# T4F81_FPGA.net
KiCad netlist of a schematic drawn in Altium Designer
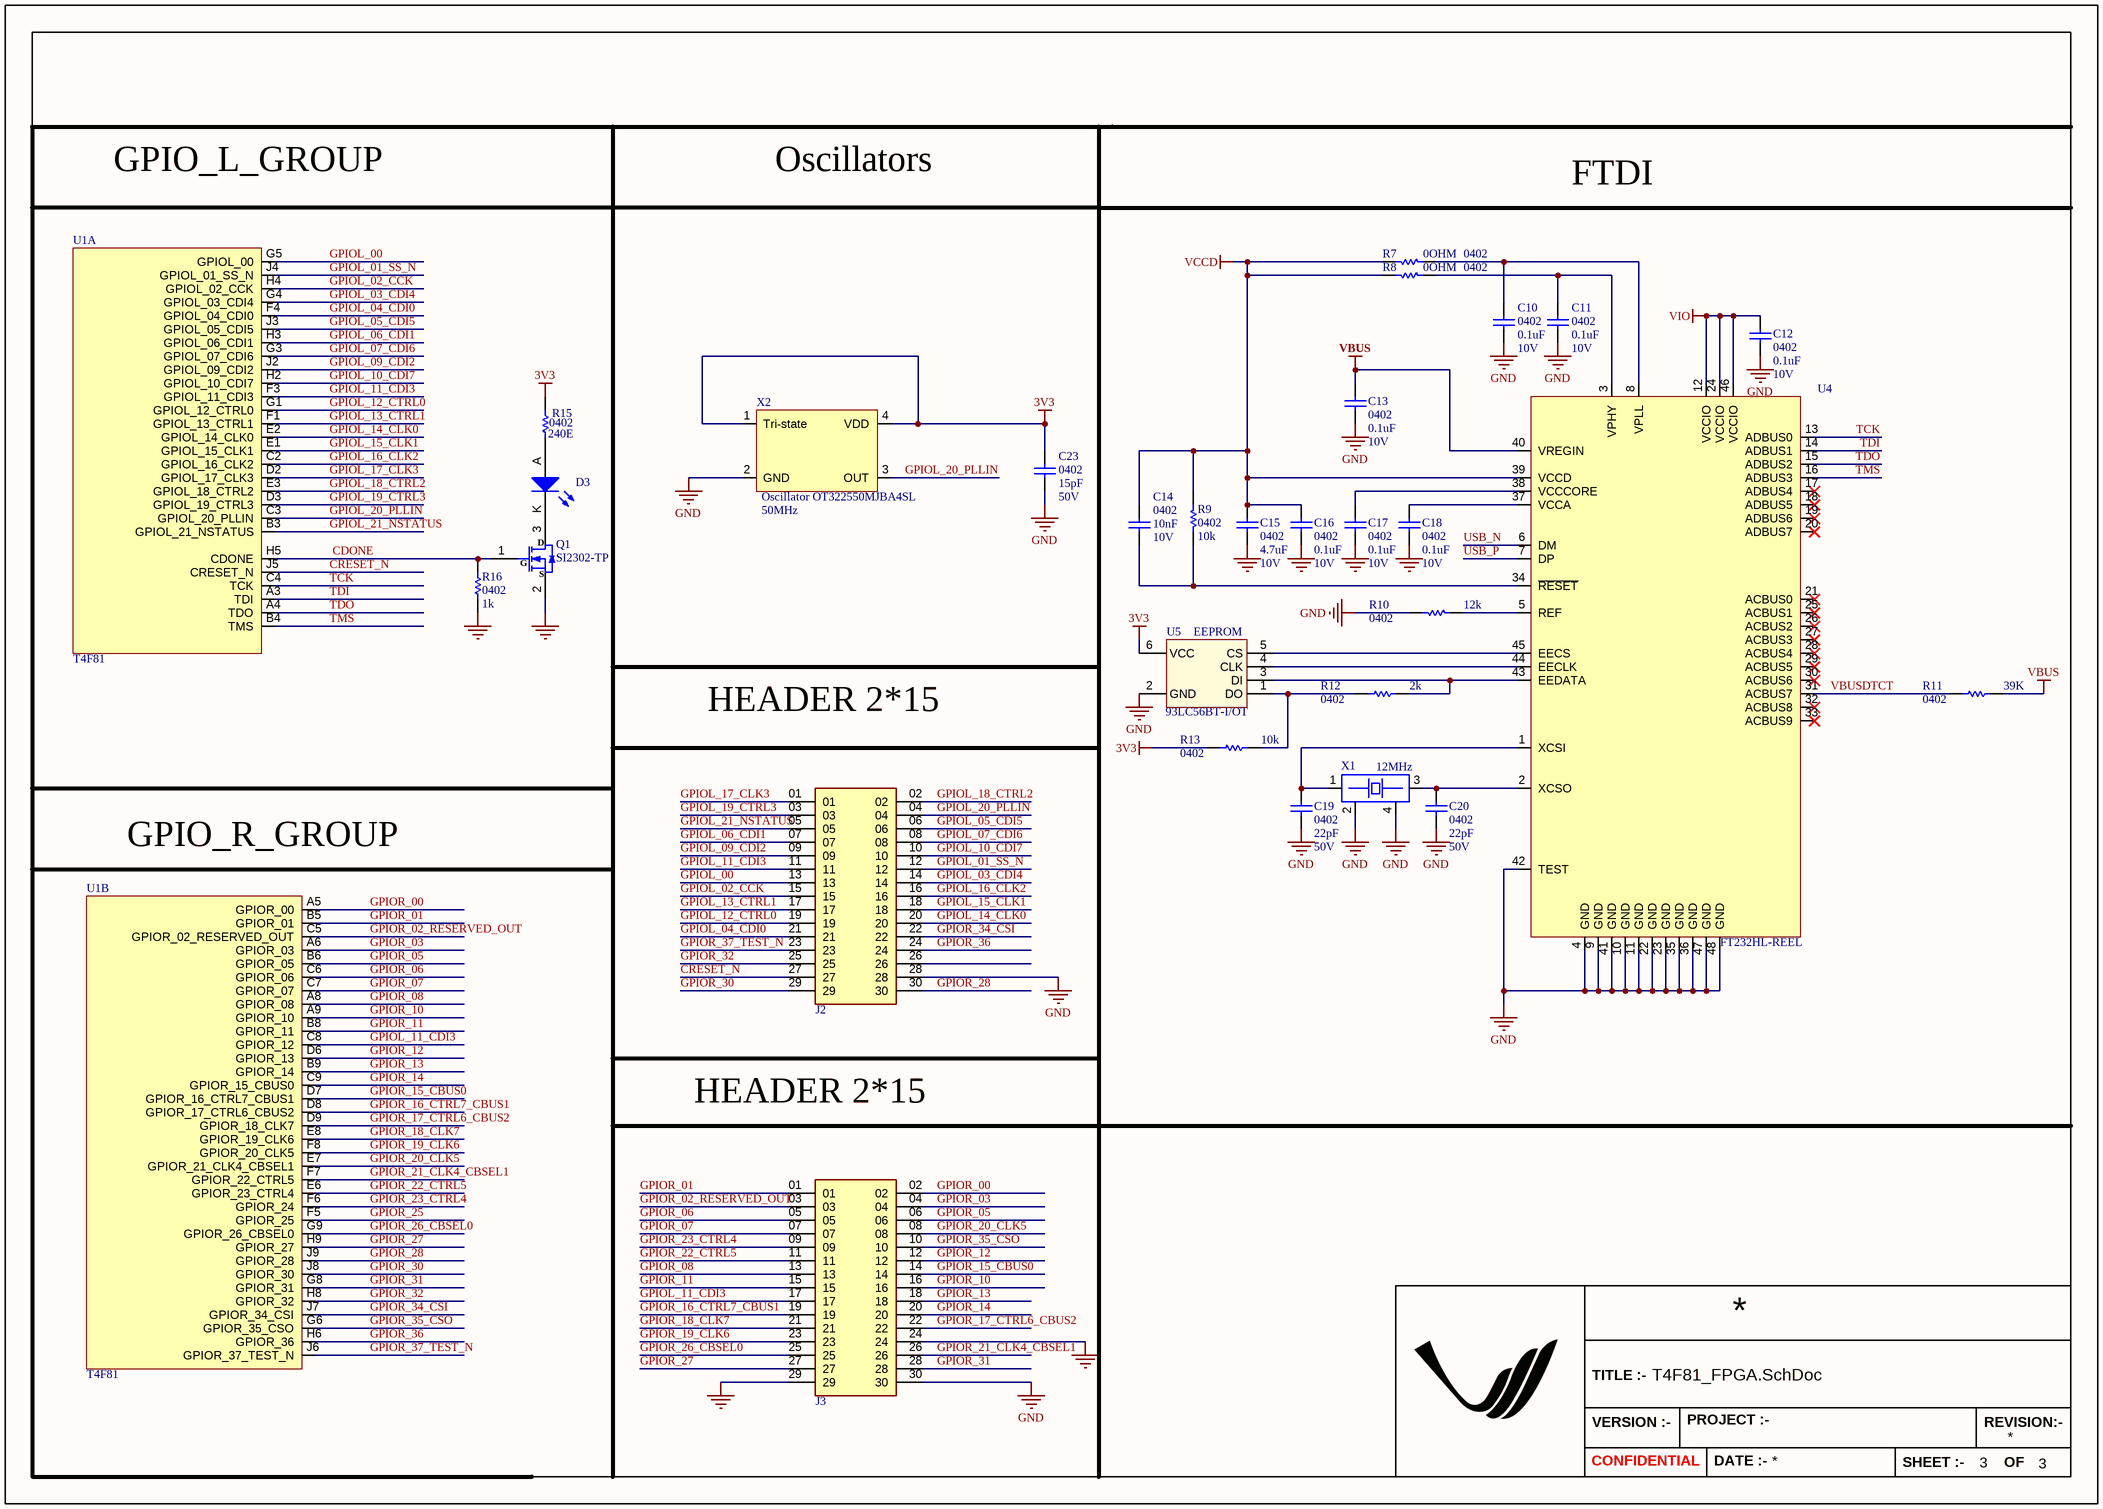
[diagram p0: T4F81_FPGA.SchDoc]

(export (version "E")
  (design (tool "Eeschema 10.0.6"))
  (components
    (comp (ref "C10")
      (value "0.1uF")
      (footprint "CAPC0402")
      (description "Ceramic Capacitor, 0.1uF, 0402,10V")
      (fields (field (name "CASE/PACKAGE") "0402") (field (name "VOLTAGE") "10V"))
      (libsource (lib "Pd's Sch Lib") (part "Capacitor"))
    )
    (comp (ref "C11")
      (value "0.1uF")
      (footprint "CAPC0402")
      (description "Ceramic Capacitor, 0.1uF, 0402,10V")
      (fields (field (name "CASE/PACKAGE") "0402") (field (name "VOLTAGE") "10V"))
      (libsource (lib "Pd's Sch Lib") (part "Capacitor"))
    )
    (comp (ref "C12")
      (value "0.1uF")
      (footprint "CAPC0402")
      (description "Ceramic Capacitor, 0.1uF, 0402,10V")
      (fields (field (name "CASE/PACKAGE") "0402") (field (name "VOLTAGE") "10V"))
      (libsource (lib "Pd's Sch Lib") (part "Capacitor"))
    )
    (comp (ref "C13")
      (value "0.1uF")
      (footprint "CAPC0402")
      (description "Ceramic Capacitor, 0.1uF, 0402,10V")
      (fields (field (name "CASE/PACKAGE") "0402") (field (name "VOLTAGE") "10V"))
      (libsource (lib "Pd's Sch Lib") (part "Capacitor"))
    )
    (comp (ref "C14")
      (value "10nF")
      (footprint "CAPC0402")
      (description "Ceramic Capacitor, 10nF, 0402,10V")
      (fields (field (name "CASE/PACKAGE") "0402") (field (name "VOLTAGE") "10V"))
      (libsource (lib "Pd's Sch Lib") (part "Capacitor"))
    )
    (comp (ref "C15")
      (value "4.7uF")
      (footprint "CAPC0402")
      (description "Ceramic Capacitor, 4.7uF, 0402,10V")
      (fields (field (name "CASE/PACKAGE") "0402") (field (name "VOLTAGE") "10V"))
      (libsource (lib "Pd's Sch Lib") (part "Capacitor"))
    )
    (comp (ref "C16")
      (value "0.1uF")
      (footprint "CAPC0402")
      (description "Ceramic Capacitor, 0.1UF, 0402,10V")
      (fields (field (name "CASE/PACKAGE") "0402") (field (name "VOLTAGE") "10V"))
      (libsource (lib "Pd's Sch Lib") (part "Capacitor"))
    )
    (comp (ref "C17")
      (value "0.1uF")
      (footprint "CAPC0402")
      (description "Ceramic Capacitor, 0.1UF, 0402,10V")
      (fields (field (name "CASE/PACKAGE") "0402") (field (name "VOLTAGE") "10V"))
      (libsource (lib "Pd's Sch Lib") (part "Capacitor"))
    )
    (comp (ref "C18")
      (value "0.1uF")
      (footprint "CAPC0402")
      (description "Ceramic Capacitor, 0.1UF, 0402,10V")
      (fields (field (name "CASE/PACKAGE") "0402") (field (name "VOLTAGE") "10V"))
      (libsource (lib "Pd's Sch Lib") (part "Capacitor"))
    )
    (comp (ref "C19")
      (value "22pF")
      (footprint "CAPC0402")
      (description "Ceramic Capacitor, 22pF, 0402,50V")
      (fields (field (name "CASE/PACKAGE") "0402") (field (name "VOLTAGE") "50V"))
      (libsource (lib "Pd's Sch Lib") (part "Capacitor"))
    )
    (comp (ref "C20")
      (value "22pF")
      (footprint "CAPC0402")
      (description "Ceramic Capacitor, 22pF, 0402,50V")
      (fields (field (name "CASE/PACKAGE") "0402") (field (name "VOLTAGE") "50V"))
      (libsource (lib "Pd's Sch Lib") (part "Capacitor"))
    )
    (comp (ref "C23")
      (value "15pF")
      (footprint "CAPC0402")
      (description "Ceramic Capacitor, 15pF, 0402,50V")
      (fields (field (name "CASE/PACKAGE") "0402") (field (name "VOLTAGE") "50V"))
      (libsource (lib "Pd's Sch Lib") (part "Capacitor"))
    )
    (comp (ref "D3")
      (value "~")
      (footprint "led_0603")
      (description "GREEN LED, 0603")
      (fields (field (name "MANUFACTURER PART NUMBER") "GREEN"))
      (libsource (lib "CUSTOM TNY290PG") (part "LED1"))
    )
    (comp (ref "J2")
      (value "Header 15X2 2.54mm")
      (footprint "Header_15X2_2.54")
      (description "Connector Header position")
      (fields (field (name "MANUFACTURER PART NUMBER") "Th P2.54MM"))
      (libsource (lib "CUSTOM SCH") (part "Header 15X2 2.54mm"))
    )
    (comp (ref "J3")
      (value "Header 15X2 2.54mm")
      (footprint "Header_15X2_2.54")
      (description "Connector Header position")
      (fields (field (name "MANUFACTURER PART NUMBER") "Th P2.54MM"))
      (libsource (lib "CUSTOM SCH") (part "Header 15X2 2.54mm"))
    )
    (comp (ref "Q1")
      (value "~")
      (footprint "SOT23-3")
      (description "N-Channel 20V 3A 1.25W (Ta) Surface Mount SOT-23")
      (fields (field (name "MANUFACTURER PART NUMBER") "SI2302-TP"))
      (libsource (lib "SchLib_SPEEDSTER7T_AC7T1500") (part "MOSFET Si2302CDS"))
    )
    (comp (ref "R7")
      (value "0OHM")
      (footprint "resc0402")
      (description "Thick Film Resistor -  0ohm, 1%, 0402")
      (fields
        (field (name "MANUFACTURER PART NUMBER") "RC0402FR-070RL")
        (field (name "CASE/PACKAGE") "0402")
        (field (name "Comment") "Res1")
      )
      (libsource (lib "Miscellaneous Devices") (part "Res1"))
    )
    (comp (ref "R8")
      (value "0OHM")
      (footprint "resc0402")
      (description "Thick Film Resistor -  0ohm, 1%, 0402")
      (fields (field (name "CASE/PACKAGE") "0402") (field (name "Comment") "Res1"))
      (libsource (lib "Miscellaneous Devices") (part "Res1"))
    )
    (comp (ref "R9")
      (value "10k")
      (footprint "RESC0402")
      (description "Thick Film Resistor -  10Kohm, 1%, 0402")
      (fields (field (name "CASE/PACKAGE") "0402") (field (name "Comment") "Res1"))
      (libsource (lib "Miscellaneous Devices") (part "Res1"))
    )
    (comp (ref "R10")
      (value "12k")
      (footprint "resc0402")
      (description "Thick Film Resistor -  12Kohm, 1%, 0402")
      (fields (field (name "CASE/PACKAGE") "0402") (field (name "Comment") "Res1"))
      (libsource (lib "Miscellaneous Devices") (part "Res1"))
    )
    (comp (ref "R11")
      (value "39K")
      (footprint "CAPC0402")
      (description "Thick Film Resistor -  39Kohm, 1%, 0402")
      (fields (field (name "CASE/PACKAGE") "0402") (field (name "Comment") "Res1"))
      (libsource (lib "Miscellaneous Devices") (part "Res1"))
    )
    (comp (ref "R12")
      (value "2k")
      (footprint "resc0402")
      (description "Thick Film Resistor -  2Kohm, 1%, 0402")
      (fields (field (name "CASE/PACKAGE") "0402") (field (name "Comment") "Res1"))
      (libsource (lib "Miscellaneous Devices") (part "Res1"))
    )
    (comp (ref "R13")
      (value "10k")
      (footprint "resc0402")
      (description "Thick Film Resistor -  10Kohm, 1%, 0402")
      (fields (field (name "CASE/PACKAGE") "0402") (field (name "Comment") "Res1"))
      (libsource (lib "Miscellaneous Devices") (part "Res1"))
    )
    (comp (ref "R15")
      (value "240E")
      (footprint "RESC0402")
      (description "Thick Film Resistor -  240ohm, 1%, 0402")
      (fields (field (name "CASE/PACKAGE") "0402"))
      (libsource (lib "CUSTOM TNY290PG") (part "Res"))
    )
    (comp (ref "R16")
      (value "1k")
      (footprint "RESC0402")
      (description "Thick Film Resistor -  1Kohm, 1%, 0402")
      (fields (field (name "CASE/PACKAGE") "0402"))
      (libsource (lib "CUSTOM TNY290PG") (part "Res"))
    )
    (comp (ref "U1") (value "T4F81") (footprint "T4F81 fpga") (libsource (lib "CUSTOM SCH") (part "T4F81")))
    (comp (ref "U4")
      (value "FTDI")
      (footprint "LQFP-48")
      (fields (field (name "MANUFACTURER PART NUMBER") "FT232HL-REEL"))
      (libsource (lib "Pd's Sch Lib") (part "FT232HL"))
    )
    (comp (ref "U5")
      (value "93LC56BT-I/OT")
      (footprint "SOT23-6")
      (description "MICROCHIP - 93LC56BT-I/OT. - 2K, 128 X 16, SERIAL EE, IND ROHS COMPLIANT: YES")
      (fields (field (name "TYPE") "EEPROM") (field (name "MANUFACTURER PART NUMBER") "93LC56BT-I/OT"))
      (libsource (lib "CUSTOM TNY290PG") (part "93LC56BT-I/OT"))
    )
    (comp (ref "X1")
      (value "XC2426TR-ND")
      (footprint "Crystal_3225")
      (description "CRYSTAL 12.0000MHZ 10PF SMD")
      (fields
        (field (name "MANUFACTURER PART NUMBER") "ECS-120-10-33B-CKM-TR")
        (field (name "FREQUENCY") "12MHz")
      )
      (libsource (lib "Pd's Sch Lib") (part "CRYSTAL_1_1"))
    )
    (comp (ref "X2")
      (value "Oscillator OT322550MJBA4SL")
      (footprint "Crystal_3225")
      (description "1.8V~3.3V -40℃~+85℃ ±10ppm 50MHz SMD3225-4P Oscillators ROHS (OT322550MJBA4SL) (C717684)")
      (fields (field (name "MANUFACTURER PART NUMBER") "OT322550MJBA4SL") (field (name "FREQUENCY") "50MHz"))
      (libsource (lib "CUSTOM SCH") (part "Oscillator OT322550MJBA4SL"))
    )
  )
  (nets
    (net (code "1") (name "/CDONE") (class "Default")
      (node (ref "Q1") (pin "1") (pinfunction "G_1") (pintype "passive"))
      (node (ref "R16") (pin "1") (pinfunction "1_1") (pintype "passive"))
      (node (ref "U1") (pin "H5") (pinfunction "CDONE_H5") (pintype "passive"))
    )
    (net (code "2") (name "/CRESET_N") (class "Default")
      (node (ref "J2") (pin "27") (pinfunction "27_27") (pintype "passive"))
      (node (ref "U1") (pin "J5") (pinfunction "CRESET_N_J5") (pintype "passive"))
    )
    (net (code "3") (name "/GPIOL_00") (class "Default")
      (node (ref "J2") (pin "13") (pinfunction "13_13") (pintype "passive"))
      (node (ref "U1") (pin "G5") (pinfunction "GPIOL_00_G5") (pintype "passive"))
    )
    (net (code "4") (name "/GPIOL_01_SS_N") (class "Default")
      (node (ref "J2") (pin "12") (pinfunction "12_12") (pintype "passive"))
      (node (ref "U1") (pin "J4") (pinfunction "GPIOL_01_SS_N_J4") (pintype "passive"))
    )
    (net (code "5") (name "/GPIOL_02_CCK") (class "Default")
      (node (ref "J2") (pin "15") (pinfunction "15_15") (pintype "passive"))
      (node (ref "U1") (pin "H4") (pinfunction "GPIOL_02_CCK_H4") (pintype "passive"))
    )
    (net (code "6") (name "/GPIOL_03_CDI4") (class "Default")
      (node (ref "J2") (pin "14") (pinfunction "14_14") (pintype "passive"))
      (node (ref "U1") (pin "G4") (pinfunction "GPIOL_03_CDI4_G4") (pintype "passive"))
    )
    (net (code "7") (name "/GPIOL_04_CDI0") (class "Default")
      (node (ref "J2") (pin "21") (pinfunction "21_21") (pintype "passive"))
      (node (ref "U1") (pin "F4") (pinfunction "GPIOL_04_CDI0_F4") (pintype "passive"))
    )
    (net (code "8") (name "/GPIOL_05_CDI5") (class "Default")
      (node (ref "J2") (pin "06") (pinfunction "06_06") (pintype "passive"))
      (node (ref "U1") (pin "J3") (pinfunction "GPIOL_05_CDI5_J3") (pintype "passive"))
    )
    (net (code "9") (name "/GPIOL_06_CDI1") (class "Default")
      (node (ref "J2") (pin "07") (pinfunction "07_07") (pintype "passive"))
      (node (ref "U1") (pin "H3") (pinfunction "GPIOL_06_CDI1_H3") (pintype "passive"))
    )
    (net (code "10") (name "/GPIOL_07_CDI6") (class "Default")
      (node (ref "J2") (pin "08") (pinfunction "08_08") (pintype "passive"))
      (node (ref "U1") (pin "G3") (pinfunction "GPIOL_07_CDI6_G3") (pintype "passive"))
    )
    (net (code "11") (name "/GPIOL_09_CDI2") (class "Default")
      (node (ref "J2") (pin "09") (pinfunction "09_09") (pintype "passive"))
      (node (ref "U1") (pin "J2") (pinfunction "GPIOL_09_CDI2_J2") (pintype "passive"))
    )
    (net (code "12") (name "/GPIOL_10_CDI7") (class "Default")
      (node (ref "J2") (pin "10") (pinfunction "10_10") (pintype "passive"))
      (node (ref "U1") (pin "H2") (pinfunction "GPIOL_10_CDI7_H2") (pintype "passive"))
    )
    (net (code "13") (name "/GPIOL_11_CDI3") (class "Default")
      (node (ref "J2") (pin "11") (pinfunction "11_11") (pintype "passive"))
      (node (ref "J3") (pin "17") (pinfunction "17_17") (pintype "passive"))
      (node (ref "U1") (pin "C8") (pinfunction "GPIOR_12_C8") (pintype "passive"))
      (node (ref "U1") (pin "F3") (pinfunction "GPIOL_11_CDI3_F3") (pintype "passive"))
    )
    (net (code "14") (name "/GPIOL_12_CTRL0") (class "Default")
      (node (ref "J2") (pin "19") (pinfunction "19_19") (pintype "passive"))
      (node (ref "U1") (pin "G1") (pinfunction "GPIOL_12_CTRL0_G1") (pintype "passive"))
    )
    (net (code "15") (name "/GPIOL_13_CTRL1") (class "Default")
      (node (ref "J2") (pin "17") (pinfunction "17_17") (pintype "passive"))
      (node (ref "U1") (pin "F1") (pinfunction "GPIOL_13_CTRL1_F1") (pintype "passive"))
    )
    (net (code "16") (name "/GPIOL_14_CLK0") (class "Default")
      (node (ref "J2") (pin "20") (pinfunction "20_20") (pintype "passive"))
      (node (ref "U1") (pin "E2") (pinfunction "GPIOL_14_CLK0_E2") (pintype "passive"))
    )
    (net (code "17") (name "/GPIOL_15_CLK1") (class "Default")
      (node (ref "J2") (pin "18") (pinfunction "18_18") (pintype "passive"))
      (node (ref "U1") (pin "E1") (pinfunction "GPIOL_15_CLK1_E1") (pintype "passive"))
    )
    (net (code "18") (name "/GPIOL_16_CLK2") (class "Default")
      (node (ref "J2") (pin "16") (pinfunction "16_16") (pintype "passive"))
      (node (ref "U1") (pin "C2") (pinfunction "GPIOL_16_CLK2_C2") (pintype "passive"))
    )
    (net (code "19") (name "/GPIOL_17_CLK3") (class "Default")
      (node (ref "J2") (pin "01") (pinfunction "01_01") (pintype "passive"))
      (node (ref "U1") (pin "D2") (pinfunction "GPIOL_17_CLK3_D2") (pintype "passive"))
    )
    (net (code "20") (name "/GPIOL_18_CTRL2") (class "Default")
      (node (ref "J2") (pin "02") (pinfunction "02_02") (pintype "passive"))
      (node (ref "U1") (pin "E3") (pinfunction "GPIOL_18_CTRL2_E3") (pintype "passive"))
    )
    (net (code "21") (name "/GPIOL_19_CTRL3") (class "Default")
      (node (ref "J2") (pin "03") (pinfunction "03_03") (pintype "passive"))
      (node (ref "U1") (pin "D3") (pinfunction "GPIOL_19_CTRL3_D3") (pintype "passive"))
    )
    (net (code "22") (name "/GPIOL_20_PLLIN") (class "Default")
      (node (ref "J2") (pin "04") (pinfunction "04_04") (pintype "passive"))
      (node (ref "U1") (pin "C3") (pinfunction "GPIOL_20_PLLIN_C3") (pintype "passive"))
      (node (ref "X2") (pin "3") (pinfunction "OUT_3") (pintype "passive"))
    )
    (net (code "23") (name "/GPIOL_21_NSTATUS") (class "Default")
      (node (ref "J2") (pin "05") (pinfunction "05_05") (pintype "passive"))
      (node (ref "U1") (pin "B3") (pinfunction "GPIOL_21_NSTATUS_B3") (pintype "passive"))
    )
    (net (code "24") (name "/GPIOR_00") (class "Default")
      (node (ref "J3") (pin "02") (pinfunction "02_02") (pintype "passive"))
      (node (ref "U1") (pin "A5") (pinfunction "GPIOR_00_A5") (pintype "passive"))
    )
    (net (code "25") (name "/GPIOR_01") (class "Default")
      (node (ref "J3") (pin "01") (pinfunction "01_01") (pintype "passive"))
      (node (ref "U1") (pin "B5") (pinfunction "GPIOR_01_B5") (pintype "passive"))
    )
    (net (code "26") (name "/GPIOR_02_RESERVED_OUT") (class "Default")
      (node (ref "J3") (pin "03") (pinfunction "03_03") (pintype "passive"))
      (node (ref "U1") (pin "C5") (pinfunction "GPIOR_02_RESERVED_OUT_C5") (pintype "passive"))
    )
    (net (code "27") (name "/GPIOR_03") (class "Default")
      (node (ref "J3") (pin "04") (pinfunction "04_04") (pintype "passive"))
      (node (ref "U1") (pin "A6") (pinfunction "GPIOR_03_A6") (pintype "passive"))
    )
    (net (code "28") (name "/GPIOR_05") (class "Default")
      (node (ref "J3") (pin "06") (pinfunction "06_06") (pintype "passive"))
      (node (ref "U1") (pin "B6") (pinfunction "GPIOR_05_B6") (pintype "passive"))
    )
    (net (code "29") (name "/GPIOR_06") (class "Default")
      (node (ref "J3") (pin "05") (pinfunction "05_05") (pintype "passive"))
      (node (ref "U1") (pin "C6") (pinfunction "GPIOR_06_C6") (pintype "passive"))
    )
    (net (code "30") (name "/GPIOR_07") (class "Default")
      (node (ref "J3") (pin "07") (pinfunction "07_07") (pintype "passive"))
      (node (ref "U1") (pin "C7") (pinfunction "GPIOR_07_C7") (pintype "passive"))
    )
    (net (code "31") (name "/GPIOR_08") (class "Default")
      (node (ref "J3") (pin "13") (pinfunction "13_13") (pintype "passive"))
      (node (ref "U1") (pin "A8") (pinfunction "GPIOR_08_A8") (pintype "passive"))
    )
    (net (code "32") (name "/GPIOR_10") (class "Default")
      (node (ref "J3") (pin "16") (pinfunction "16_16") (pintype "passive"))
      (node (ref "U1") (pin "A9") (pinfunction "GPIOR_10_A9") (pintype "passive"))
    )
    (net (code "33") (name "/GPIOR_11") (class "Default")
      (node (ref "J3") (pin "15") (pinfunction "15_15") (pintype "passive"))
      (node (ref "U1") (pin "B8") (pinfunction "GPIOR_11_B8") (pintype "passive"))
    )
    (net (code "34") (name "/GPIOR_12") (class "Default")
      (node (ref "J3") (pin "12") (pinfunction "12_12") (pintype "passive"))
      (node (ref "U1") (pin "D6") (pinfunction "GPIOR_13_D6") (pintype "passive"))
    )
    (net (code "35") (name "/GPIOR_13") (class "Default")
      (node (ref "J3") (pin "18") (pinfunction "18_18") (pintype "passive"))
      (node (ref "U1") (pin "B9") (pinfunction "GPIOR_14_B9") (pintype "passive"))
    )
    (net (code "36") (name "/GPIOR_14") (class "Default")
      (node (ref "J3") (pin "20") (pinfunction "20_20") (pintype "passive"))
      (node (ref "U1") (pin "C9") (pinfunction "GPIOR_15_CBUS0_C9") (pintype "passive"))
    )
    (net (code "37") (name "/GPIOR_15_CBUS0") (class "Default")
      (node (ref "J3") (pin "14") (pinfunction "14_14") (pintype "passive"))
      (node (ref "U1") (pin "D7") (pinfunction "GPIOR_16_CTRL7_CBUS1_D7") (pintype "passive"))
    )
    (net (code "38") (name "/GPIOR_16_CTRL7_CBUS1") (class "Default")
      (node (ref "J3") (pin "19") (pinfunction "19_19") (pintype "passive"))
      (node (ref "U1") (pin "D8") (pinfunction "GPIOR_17_CTRL6_CBUS2_D8") (pintype "passive"))
    )
    (net (code "39") (name "/GPIOR_17_CTRL6_CBUS2") (class "Default")
      (node (ref "J3") (pin "22") (pinfunction "22_22") (pintype "passive"))
      (node (ref "U1") (pin "D9") (pinfunction "GPIOR_18_CLK7_D9") (pintype "passive"))
    )
    (net (code "40") (name "/GPIOR_18_CLK7") (class "Default")
      (node (ref "J3") (pin "21") (pinfunction "21_21") (pintype "passive"))
      (node (ref "U1") (pin "E8") (pinfunction "GPIOR_19_CLK6_E8") (pintype "passive"))
    )
    (net (code "41") (name "/GPIOR_19_CLK6") (class "Default")
      (node (ref "J3") (pin "23") (pinfunction "23_23") (pintype "passive"))
      (node (ref "U1") (pin "F8") (pinfunction "GPIOR_20_CLK5_F8") (pintype "passive"))
    )
    (net (code "42") (name "/GPIOR_20_CLK5") (class "Default")
      (node (ref "J3") (pin "08") (pinfunction "08_08") (pintype "passive"))
      (node (ref "U1") (pin "E7") (pinfunction "GPIOR_21_CLK4_CBSEL1_E7") (pintype "passive"))
    )
    (net (code "43") (name "/GPIOR_21_CLK4_CBSEL1") (class "Default")
      (node (ref "J3") (pin "26") (pinfunction "26_26") (pintype "passive"))
      (node (ref "U1") (pin "F7") (pinfunction "GPIOR_22_CTRL5_F7") (pintype "passive"))
    )
    (net (code "44") (name "/GPIOR_22_CTRL5") (class "Default")
      (node (ref "J3") (pin "11") (pinfunction "11_11") (pintype "passive"))
      (node (ref "U1") (pin "E6") (pinfunction "GPIOR_23_CTRL4_E6") (pintype "passive"))
    )
    (net (code "45") (name "/GPIOR_23_CTRL4") (class "Default")
      (node (ref "J3") (pin "09") (pinfunction "09_09") (pintype "passive"))
      (node (ref "U1") (pin "F6") (pinfunction "GPIOR_24_F6") (pintype "passive"))
    )
    (net (code "46") (name "/GPIOR_25") (class "Default")
      (node (ref "U1") (pin "F5") (pinfunction "GPIOR_25_F5") (pintype "passive"))
    )
    (net (code "47") (name "/GPIOR_26_CBSEL0") (class "Default")
      (node (ref "J3") (pin "25") (pinfunction "25_25") (pintype "passive"))
      (node (ref "U1") (pin "G9") (pinfunction "GPIOR_26_CBSEL0_G9") (pintype "passive"))
    )
    (net (code "48") (name "/GPIOR_27") (class "Default")
      (node (ref "J3") (pin "27") (pinfunction "27_27") (pintype "passive"))
      (node (ref "U1") (pin "H9") (pinfunction "GPIOR_27_H9") (pintype "passive"))
    )
    (net (code "49") (name "/GPIOR_28") (class "Default")
      (node (ref "J2") (pin "30") (pinfunction "30_30") (pintype "passive"))
      (node (ref "U1") (pin "J9") (pinfunction "GPIOR_28_J9") (pintype "passive"))
    )
    (net (code "50") (name "/GPIOR_30") (class "Default")
      (node (ref "J2") (pin "29") (pinfunction "29_29") (pintype "passive"))
      (node (ref "U1") (pin "J8") (pinfunction "GPIOR_30_J8") (pintype "passive"))
    )
    (net (code "51") (name "/GPIOR_31") (class "Default")
      (node (ref "J3") (pin "28") (pinfunction "28_28") (pintype "passive"))
      (node (ref "U1") (pin "G8") (pinfunction "GPIOR_31_G8") (pintype "passive"))
    )
    (net (code "52") (name "/GPIOR_32") (class "Default")
      (node (ref "J2") (pin "25") (pinfunction "25_25") (pintype "passive"))
      (node (ref "U1") (pin "H8") (pinfunction "GPIOR_32_H8") (pintype "passive"))
    )
    (net (code "53") (name "/GPIOR_34_CSI") (class "Default")
      (node (ref "J2") (pin "22") (pinfunction "22_22") (pintype "passive"))
      (node (ref "U1") (pin "J7") (pinfunction "GPIOR_34_CSI_J7") (pintype "passive"))
    )
    (net (code "54") (name "/GPIOR_35_CSO") (class "Default")
      (node (ref "J3") (pin "10") (pinfunction "10_10") (pintype "passive"))
      (node (ref "U1") (pin "G6") (pinfunction "GPIOR_35_CSO_G6") (pintype "passive"))
    )
    (net (code "55") (name "/GPIOR_36") (class "Default")
      (node (ref "J2") (pin "24") (pinfunction "24_24") (pintype "passive"))
      (node (ref "U1") (pin "H6") (pinfunction "GPIOR_36_H6") (pintype "passive"))
    )
    (net (code "56") (name "/GPIOR_37_TEST_N") (class "Default")
      (node (ref "J2") (pin "23") (pinfunction "23_23") (pintype "passive"))
      (node (ref "U1") (pin "J6") (pinfunction "GPIOR_37_TEST_N_J6") (pintype "passive"))
    )
    (net (code "57") (name "/TCK") (class "Default")
      (node (ref "U1") (pin "C4") (pinfunction "TCK_C4") (pintype "passive"))
      (node (ref "U4") (pin "13") (pinfunction "ADBUS0_13") (pintype "passive"))
    )
    (net (code "58") (name "/TDI") (class "Default")
      (node (ref "U1") (pin "A3") (pinfunction "TDI_A3") (pintype "passive"))
      (node (ref "U4") (pin "14") (pinfunction "ADBUS1_14") (pintype "passive"))
    )
    (net (code "59") (name "/TDO") (class "Default")
      (node (ref "U1") (pin "A4") (pinfunction "TDO_A4") (pintype "passive"))
      (node (ref "U4") (pin "15") (pinfunction "ADBUS2_15") (pintype "passive"))
    )
    (net (code "60") (name "/TMS") (class "Default")
      (node (ref "U1") (pin "B4") (pinfunction "TMS_B4") (pintype "passive"))
      (node (ref "U4") (pin "16") (pinfunction "ADBUS3_16") (pintype "passive"))
    )
    (net (code "61") (name "/USB_N") (class "Default")
      (node (ref "U4") (pin "6") (pinfunction "DM_6") (pintype "passive"))
    )
    (net (code "62") (name "/USB_P") (class "Default")
      (node (ref "U4") (pin "7") (pinfunction "DP_7") (pintype "passive"))
    )
    (net (code "63") (name "/VBUSDTCT") (class "Default")
      (node (ref "R11") (pin "2") (pinfunction "2_2") (pintype "passive"))
      (node (ref "U4") (pin "31") (pinfunction "ACBUS7_31") (pintype "passive"))
    )
    (net (code "64") (name "3V3") (class "Default")
      (node (ref "C23") (pin "2") (pinfunction "2_2") (pintype "passive"))
      (node (ref "R13") (pin "1") (pinfunction "1_1") (pintype "passive"))
      (node (ref "R15") (pin "2") (pinfunction "2_2") (pintype "passive"))
      (node (ref "U5") (pin "6") (pinfunction "VCC_6") (pintype "passive"))
      (node (ref "X2") (pin "1") (pinfunction "Tri-state_1") (pintype "passive"))
      (node (ref "X2") (pin "4") (pinfunction "VDD_4") (pintype "passive"))
    )
    (net (code "65") (name "GND") (class "Default")
      (node (ref "C10") (pin "1") (pinfunction "1_1") (pintype "passive"))
      (node (ref "C11") (pin "1") (pinfunction "1_1") (pintype "passive"))
      (node (ref "C12") (pin "1") (pinfunction "1_1") (pintype "passive"))
      (node (ref "C13") (pin "1") (pinfunction "1_1") (pintype "passive"))
      (node (ref "C15") (pin "1") (pinfunction "1_1") (pintype "passive"))
      (node (ref "C16") (pin "1") (pinfunction "1_1") (pintype "passive"))
      (node (ref "C17") (pin "1") (pinfunction "1_1") (pintype "passive"))
      (node (ref "C18") (pin "1") (pinfunction "1_1") (pintype "passive"))
      (node (ref "C19") (pin "1") (pinfunction "1_1") (pintype "passive"))
      (node (ref "C20") (pin "1") (pinfunction "1_1") (pintype "passive"))
      (node (ref "C23") (pin "1") (pinfunction "1_1") (pintype "passive"))
      (node (ref "J2") (pin "28") (pinfunction "28_28") (pintype "passive"))
      (node (ref "J3") (pin "24") (pinfunction "24_24") (pintype "passive"))
      (node (ref "J3") (pin "29") (pinfunction "29_29") (pintype "passive"))
      (node (ref "J3") (pin "30") (pinfunction "30_30") (pintype "passive"))
      (node (ref "Q1") (pin "2") (pinfunction "S_2") (pintype "passive"))
      (node (ref "R10") (pin "1") (pinfunction "1_1") (pintype "passive"))
      (node (ref "R16") (pin "2") (pinfunction "2_2") (pintype "passive"))
      (node (ref "U4") (pin "10") (pinfunction "GND_10") (pintype "passive"))
      (node (ref "U4") (pin "11") (pinfunction "GND_11") (pintype "passive"))
      (node (ref "U4") (pin "22") (pinfunction "GND_22") (pintype "passive"))
      (node (ref "U4") (pin "23") (pinfunction "GND_23") (pintype "passive"))
      (node (ref "U4") (pin "35") (pinfunction "GND_35") (pintype "passive"))
      (node (ref "U4") (pin "36") (pinfunction "GND_36") (pintype "passive"))
      (node (ref "U4") (pin "4") (pinfunction "GND_4") (pintype "passive"))
      (node (ref "U4") (pin "41") (pinfunction "GND_41") (pintype "passive"))
      (node (ref "U4") (pin "42") (pinfunction "TEST_42") (pintype "passive"))
      (node (ref "U4") (pin "47") (pinfunction "GND_47") (pintype "passive"))
      (node (ref "U4") (pin "48") (pinfunction "GND_48") (pintype "passive"))
      (node (ref "U4") (pin "9") (pinfunction "GND_9") (pintype "passive"))
      (node (ref "U5") (pin "2") (pinfunction "GND_2") (pintype "passive"))
      (node (ref "X1") (pin "2") (pinfunction "2_2") (pintype "passive"))
      (node (ref "X1") (pin "4") (pinfunction "4_4") (pintype "passive"))
      (node (ref "X2") (pin "2") (pinfunction "GND_2") (pintype "passive"))
    )
    (net (code "66") (name "Net-(D3-PadA)") (class "Default")
      (node (ref "D3") (pin "A") (pinfunction "A_A") (pintype "passive"))
      (node (ref "R15") (pin "1") (pinfunction "1_1") (pintype "passive"))
    )
    (net (code "67") (name "Net-(Q1-D)") (class "Default")
      (node (ref "D3") (pin "K") (pinfunction "K_K") (pintype "passive"))
      (node (ref "Q1") (pin "3") (pinfunction "D_3") (pintype "passive"))
    )
    (net (code "68") (name "Net-(U4-EECLK)") (class "Default")
      (node (ref "U4") (pin "44") (pinfunction "EECLK_44") (pintype "passive"))
      (node (ref "U5") (pin "4") (pinfunction "CLK_4") (pintype "passive"))
    )
    (net (code "69") (name "Net-(U4-EECS)") (class "Default")
      (node (ref "U4") (pin "45") (pinfunction "EECS_45") (pintype "passive"))
      (node (ref "U5") (pin "5") (pinfunction "CS_5") (pintype "passive"))
    )
    (net (code "70") (name "Net-(U4-EEDATA)") (class "Default")
      (node (ref "R12") (pin "2") (pinfunction "2_2") (pintype "passive"))
      (node (ref "U4") (pin "43") (pinfunction "EEDATA_43") (pintype "passive"))
      (node (ref "U5") (pin "3") (pinfunction "DI_3") (pintype "passive"))
    )
    (net (code "71") (name "Net-(U4-REF)") (class "Default")
      (node (ref "R10") (pin "2") (pinfunction "2_2") (pintype "passive"))
      (node (ref "U4") (pin "5") (pinfunction "REF_5") (pintype "passive"))
    )
    (net (code "72") (name "Net-(U4-VCCA)") (class "Default")
      (node (ref "C18") (pin "2") (pinfunction "2_2") (pintype "passive"))
      (node (ref "U4") (pin "37") (pinfunction "VCCA_37") (pintype "passive"))
    )
    (net (code "73") (name "Net-(U4-VCCCORE)") (class "Default")
      (node (ref "C17") (pin "2") (pinfunction "2_2") (pintype "passive"))
      (node (ref "U4") (pin "38") (pinfunction "VCCCORE_38") (pintype "passive"))
    )
    (net (code "74") (name "Net-(U4-VPHY)") (class "Default")
      (node (ref "C11") (pin "2") (pinfunction "2_2") (pintype "passive"))
      (node (ref "R8") (pin "1") (pinfunction "1_1") (pintype "passive"))
      (node (ref "U4") (pin "3") (pinfunction "VPHY_3") (pintype "passive"))
    )
    (net (code "75") (name "Net-(U4-VPLL)") (class "Default")
      (node (ref "C10") (pin "2") (pinfunction "2_2") (pintype "passive"))
      (node (ref "R7") (pin "1") (pinfunction "1_1") (pintype "passive"))
      (node (ref "U4") (pin "8") (pinfunction "VPLL_8") (pintype "passive"))
    )
    (net (code "76") (name "Net-(U4-XCSI)") (class "Default")
      (node (ref "C19") (pin "2") (pinfunction "2_2") (pintype "passive"))
      (node (ref "U4") (pin "1") (pinfunction "XCSI_1") (pintype "passive"))
      (node (ref "X1") (pin "1") (pinfunction "1_1") (pintype "passive"))
    )
    (net (code "77") (name "Net-(U4-XCSO)") (class "Default")
      (node (ref "C20") (pin "2") (pinfunction "2_2") (pintype "passive"))
      (node (ref "U4") (pin "2") (pinfunction "XCSO_2") (pintype "passive"))
      (node (ref "X1") (pin "3") (pinfunction "3_3") (pintype "passive"))
    )
    (net (code "78") (name "Net-(U4-~{RESET})") (class "Default")
      (node (ref "C14") (pin "1") (pinfunction "1_1") (pintype "passive"))
      (node (ref "R9") (pin "1") (pinfunction "1_1") (pintype "passive"))
      (node (ref "U4") (pin "34") (pinfunction "~{RESET}_34") (pintype "passive"))
    )
    (net (code "79") (name "Net-(U5-DO)") (class "Default")
      (node (ref "R12") (pin "1") (pinfunction "1_1") (pintype "passive"))
      (node (ref "R13") (pin "2") (pinfunction "2_2") (pintype "passive"))
      (node (ref "U5") (pin "1") (pinfunction "DO_1") (pintype "passive"))
    )
    (net (code "80") (name "VBUS") (class "Default")
      (node (ref "C13") (pin "2") (pinfunction "2_2") (pintype "passive"))
      (node (ref "R11") (pin "1") (pinfunction "1_1") (pintype "passive"))
      (node (ref "U4") (pin "40") (pinfunction "VREGIN_40") (pintype "passive"))
    )
    (net (code "81") (name "VCCD") (class "Default")
      (node (ref "C14") (pin "2") (pinfunction "2_2") (pintype "passive"))
      (node (ref "C15") (pin "2") (pinfunction "2_2") (pintype "passive"))
      (node (ref "C16") (pin "2") (pinfunction "2_2") (pintype "passive"))
      (node (ref "R7") (pin "2") (pinfunction "2_2") (pintype "passive"))
      (node (ref "R8") (pin "2") (pinfunction "2_2") (pintype "passive"))
      (node (ref "R9") (pin "2") (pinfunction "2_2") (pintype "passive"))
      (node (ref "U4") (pin "39") (pinfunction "VCCD_39") (pintype "passive"))
    )
    (net (code "82") (name "VIO") (class "Default")
      (node (ref "C12") (pin "2") (pinfunction "2_2") (pintype "passive"))
      (node (ref "U4") (pin "12") (pinfunction "VCCIO_12") (pintype "passive"))
      (node (ref "U4") (pin "24") (pinfunction "VCCIO_24") (pintype "passive"))
      (node (ref "U4") (pin "46") (pinfunction "VCCIO_46") (pintype "passive"))
    )
    (net (code "83") (name "unconnected-(J2-Pad26)") (class "Default")
      (node (ref "J2") (pin "26") (pinfunction "26_26") (pintype "passive"))
    )
    (net (code "84") (name "unconnected-(U4-ACBUS0-Pad21)") (class "Default")
      (node (ref "U4") (pin "21") (pinfunction "ACBUS0_21") (pintype "passive+no_connect"))
    )
    (net (code "85") (name "unconnected-(U4-ACBUS1-Pad25)") (class "Default")
      (node (ref "U4") (pin "25") (pinfunction "ACBUS1_25") (pintype "passive+no_connect"))
    )
    (net (code "86") (name "unconnected-(U4-ACBUS2-Pad26)") (class "Default")
      (node (ref "U4") (pin "26") (pinfunction "ACBUS2_26") (pintype "passive+no_connect"))
    )
    (net (code "87") (name "unconnected-(U4-ACBUS3-Pad27)") (class "Default")
      (node (ref "U4") (pin "27") (pinfunction "ACBUS3_27") (pintype "passive+no_connect"))
    )
    (net (code "88") (name "unconnected-(U4-ACBUS4-Pad28)") (class "Default")
      (node (ref "U4") (pin "28") (pinfunction "ACBUS4_28") (pintype "passive+no_connect"))
    )
    (net (code "89") (name "unconnected-(U4-ACBUS5-Pad29)") (class "Default")
      (node (ref "U4") (pin "29") (pinfunction "ACBUS5_29") (pintype "passive+no_connect"))
    )
    (net (code "90") (name "unconnected-(U4-ACBUS6-Pad30)") (class "Default")
      (node (ref "U4") (pin "30") (pinfunction "ACBUS6_30") (pintype "passive+no_connect"))
    )
    (net (code "91") (name "unconnected-(U4-ACBUS8-Pad32)") (class "Default")
      (node (ref "U4") (pin "32") (pinfunction "ACBUS8_32") (pintype "passive+no_connect"))
    )
    (net (code "92") (name "unconnected-(U4-ACBUS9-Pad33)") (class "Default")
      (node (ref "U4") (pin "33") (pinfunction "ACBUS9_33") (pintype "passive+no_connect"))
    )
    (net (code "93") (name "unconnected-(U4-ADBUS4-Pad17)") (class "Default")
      (node (ref "U4") (pin "17") (pinfunction "ADBUS4_17") (pintype "passive+no_connect"))
    )
    (net (code "94") (name "unconnected-(U4-ADBUS5-Pad18)") (class "Default")
      (node (ref "U4") (pin "18") (pinfunction "ADBUS5_18") (pintype "passive+no_connect"))
    )
    (net (code "95") (name "unconnected-(U4-ADBUS6-Pad19)") (class "Default")
      (node (ref "U4") (pin "19") (pinfunction "ADBUS6_19") (pintype "passive+no_connect"))
    )
    (net (code "96") (name "unconnected-(U4-ADBUS7-Pad20)") (class "Default")
      (node (ref "U4") (pin "20") (pinfunction "ADBUS7_20") (pintype "passive+no_connect"))
    )
  )
)
